# GaugeRev2.net
KiCad netlist of a schematic drawn in EAGLE
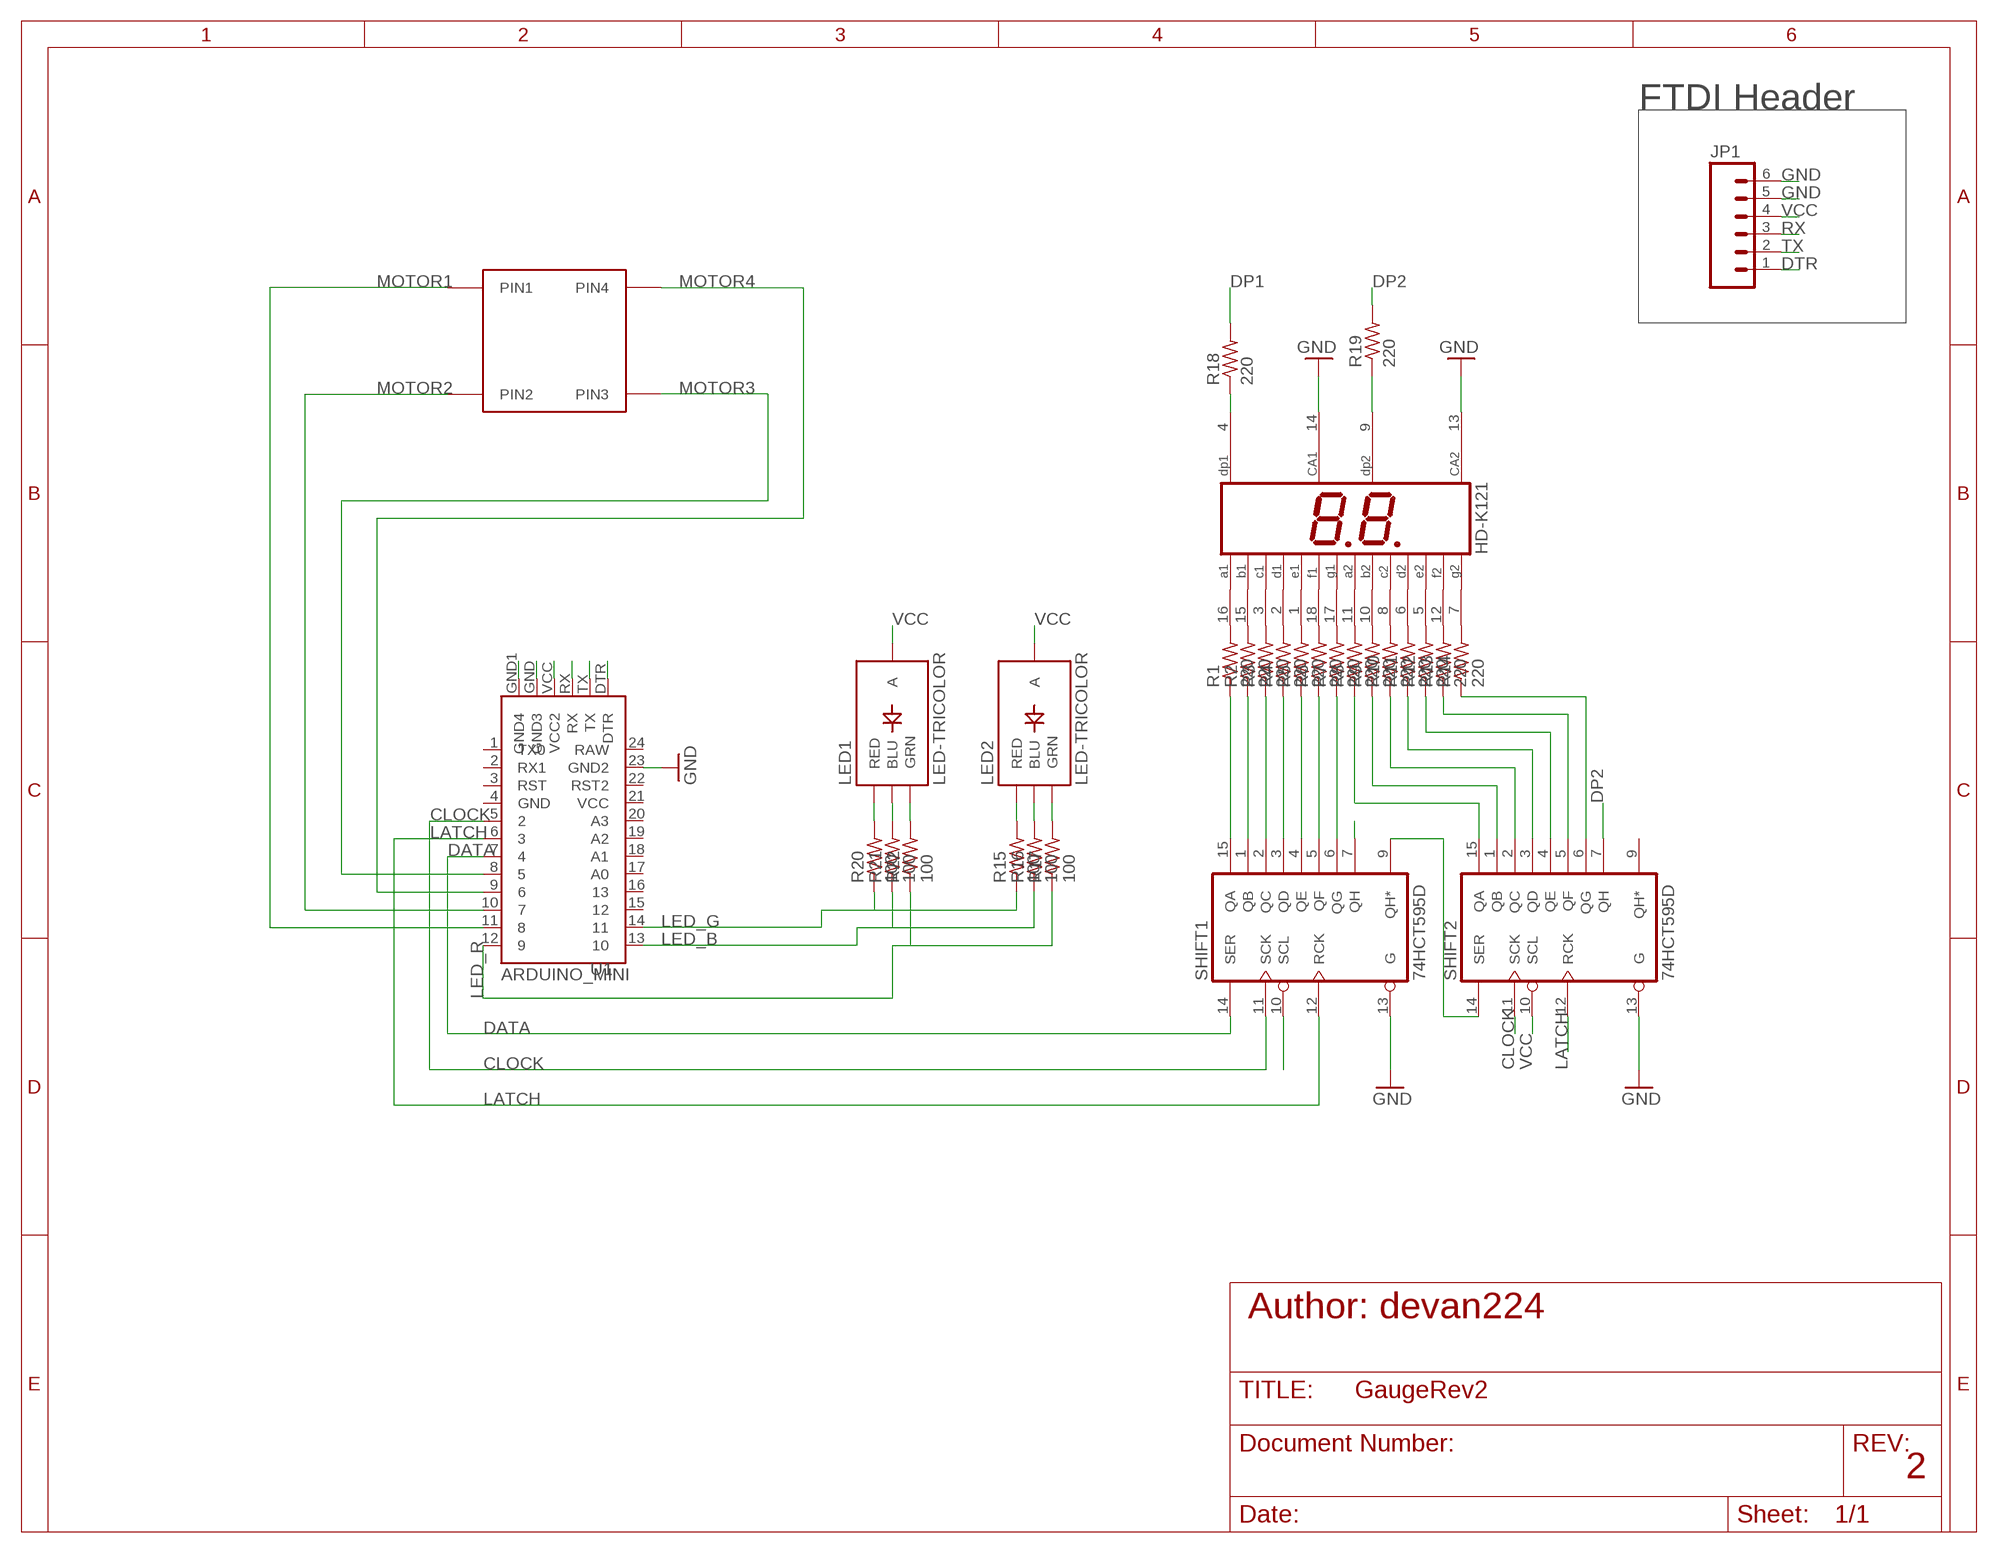
[diagram p0: schematic, sheet 1]

(export (version "E")
  (design (tool "Eeschema 10.0.6"))
  (components
    (comp (ref "DIS2")
      (value "HD-K121")
      (footprint "eagle-import:HDSP-R")
      (libsource (lib "eagle-import") (part "HD-K121"))
    )
    (comp (ref "JP1")
      (value "M06SIP")
      (footprint "eagle-import:1X06")
      (libsource (lib "eagle-import") (part "M06SIP"))
    )
    (comp (ref "LED1")
      (value "LED-TRICOLOR")
      (footprint "eagle-import:LED-TRICOLOR-SMD")
      (libsource (lib "eagle-import") (part "LED-TRICOLOR"))
    )
    (comp (ref "LED2")
      (value "LED-TRICOLOR")
      (footprint "eagle-import:LED-TRICOLOR-SMD")
      (libsource (lib "eagle-import") (part "LED-TRICOLOR"))
    )
    (comp (ref "R1")
      (value "220")
      (footprint "eagle-import:R1206")
      (libsource (lib "eagle-import") (part "R-US_R1206"))
    )
    (comp (ref "R2")
      (value "220")
      (footprint "eagle-import:R1206")
      (libsource (lib "eagle-import") (part "R-US_R1206"))
    )
    (comp (ref "R3")
      (value "220")
      (footprint "eagle-import:R1206")
      (libsource (lib "eagle-import") (part "R-US_R1206"))
    )
    (comp (ref "R4")
      (value "220")
      (footprint "eagle-import:R1206")
      (libsource (lib "eagle-import") (part "R-US_R1206"))
    )
    (comp (ref "R5")
      (value "220")
      (footprint "eagle-import:R1206")
      (libsource (lib "eagle-import") (part "R-US_R1206"))
    )
    (comp (ref "R6")
      (value "220")
      (footprint "eagle-import:R1206")
      (libsource (lib "eagle-import") (part "R-US_R1206"))
    )
    (comp (ref "R7")
      (value "220")
      (footprint "eagle-import:R1206")
      (libsource (lib "eagle-import") (part "R-US_R1206"))
    )
    (comp (ref "R8")
      (value "220")
      (footprint "eagle-import:R1206")
      (libsource (lib "eagle-import") (part "R-US_R1206"))
    )
    (comp (ref "R9")
      (value "220")
      (footprint "eagle-import:R1206")
      (libsource (lib "eagle-import") (part "R-US_R1206"))
    )
    (comp (ref "R10")
      (value "220")
      (footprint "eagle-import:R1206")
      (libsource (lib "eagle-import") (part "R-US_R1206"))
    )
    (comp (ref "R11")
      (value "220")
      (footprint "eagle-import:R1206")
      (libsource (lib "eagle-import") (part "R-US_R1206"))
    )
    (comp (ref "R12")
      (value "220")
      (footprint "eagle-import:R1206")
      (libsource (lib "eagle-import") (part "R-US_R1206"))
    )
    (comp (ref "R13")
      (value "220")
      (footprint "eagle-import:R1206")
      (libsource (lib "eagle-import") (part "R-US_R1206"))
    )
    (comp (ref "R14")
      (value "220")
      (footprint "eagle-import:R1206")
      (libsource (lib "eagle-import") (part "R-US_R1206"))
    )
    (comp (ref "R15")
      (value "100")
      (footprint "eagle-import:R1206")
      (libsource (lib "eagle-import") (part "R-US_R1206"))
    )
    (comp (ref "R16")
      (value "100")
      (footprint "eagle-import:R1206")
      (libsource (lib "eagle-import") (part "R-US_R1206"))
    )
    (comp (ref "R17")
      (value "100")
      (footprint "eagle-import:R1206")
      (libsource (lib "eagle-import") (part "R-US_R1206"))
    )
    (comp (ref "R18")
      (value "220")
      (footprint "eagle-import:R1206")
      (libsource (lib "eagle-import") (part "R-US_R1206"))
    )
    (comp (ref "R19")
      (value "220")
      (footprint "eagle-import:R1206")
      (libsource (lib "eagle-import") (part "R-US_R1206"))
    )
    (comp (ref "R20")
      (value "100")
      (footprint "eagle-import:R1206")
      (libsource (lib "eagle-import") (part "R-US_R1206"))
    )
    (comp (ref "R21")
      (value "100")
      (footprint "eagle-import:R1206")
      (libsource (lib "eagle-import") (part "R-US_R1206"))
    )
    (comp (ref "R22")
      (value "100")
      (footprint "eagle-import:R1206")
      (libsource (lib "eagle-import") (part "R-US_R1206"))
    )
    (comp (ref "SHIFT1")
      (value "74HCT595D")
      (footprint "eagle-import:SO16")
      (libsource (lib "eagle-import") (part "74595DHCT"))
    )
    (comp (ref "SHIFT2")
      (value "74HCT595D")
      (footprint "eagle-import:SO16")
      (libsource (lib "eagle-import") (part "74595DHCT"))
    )
    (comp (ref "U1")
      (value "ARDUINO_MINI")
      (footprint "eagle-import:ARDUINO_MINI")
      (libsource (lib "eagle-import") (part "ARDUINO_MINI"))
    )
    (comp (ref "U2")
      (value "VID29")
      (footprint "eagle-import:VID29")
      (libsource (lib "eagle-import") (part "VID29"))
    )
  )
  (nets
    (net (code "1") (name "/CLOCK") (class "Default")
      (node (ref "SHIFT1") (pin "11") (pinfunction "SCK_11") (pintype "input"))
      (node (ref "SHIFT2") (pin "11") (pinfunction "SCK_11") (pintype "input"))
      (node (ref "U1") (pin "5") (pinfunction "2_5") (pintype "bidirectional"))
    )
    (net (code "2") (name "/DATA") (class "Default")
      (node (ref "SHIFT1") (pin "14") (pinfunction "SER_14") (pintype "input"))
      (node (ref "U1") (pin "7") (pinfunction "4_7") (pintype "bidirectional"))
    )
    (net (code "3") (name "/DP1") (class "Default")
      (node (ref "R18") (pin "2") (pinfunction "2_2") (pintype "passive"))
      (node (ref "SHIFT1") (pin "7") (pinfunction "QH_7") (pintype "tri_state"))
    )
    (net (code "4") (name "/DP2") (class "Default")
      (node (ref "R19") (pin "2") (pinfunction "2_2") (pintype "passive"))
      (node (ref "SHIFT2") (pin "7") (pinfunction "QH_7") (pintype "tri_state"))
    )
    (net (code "5") (name "/DTR") (class "Default")
      (node (ref "JP1") (pin "1") (pinfunction "1_1") (pintype "passive"))
      (node (ref "U1") (pin "DTR") (pinfunction "DTR_DTR") (pintype "bidirectional"))
    )
    (net (code "6") (name "/LATCH") (class "Default")
      (node (ref "SHIFT1") (pin "12") (pinfunction "RCK_12") (pintype "input"))
      (node (ref "SHIFT2") (pin "12") (pinfunction "RCK_12") (pintype "input"))
      (node (ref "U1") (pin "6") (pinfunction "3_6") (pintype "bidirectional"))
    )
    (net (code "7") (name "/LED_B") (class "Default")
      (node (ref "R16") (pin "1") (pinfunction "1_1") (pintype "passive"))
      (node (ref "R21") (pin "1") (pinfunction "1_1") (pintype "passive"))
      (node (ref "U1") (pin "13") (pinfunction "10_13") (pintype "bidirectional"))
    )
    (net (code "8") (name "/LED_G") (class "Default")
      (node (ref "R15") (pin "1") (pinfunction "1_1") (pintype "passive"))
      (node (ref "R20") (pin "1") (pinfunction "1_1") (pintype "passive"))
      (node (ref "U1") (pin "14") (pinfunction "11_14") (pintype "bidirectional"))
    )
    (net (code "9") (name "/LED_R") (class "Default")
      (node (ref "R17") (pin "1") (pinfunction "1_1") (pintype "passive"))
      (node (ref "R22") (pin "1") (pinfunction "1_1") (pintype "passive"))
      (node (ref "U1") (pin "12") (pinfunction "9_12") (pintype "bidirectional"))
    )
    (net (code "10") (name "/MOTOR1") (class "Default")
      (node (ref "U1") (pin "11") (pinfunction "8_11") (pintype "bidirectional"))
      (node (ref "U2") (pin "PIN1") (pinfunction "PIN1_PIN1") (pintype "bidirectional"))
    )
    (net (code "11") (name "/MOTOR2") (class "Default")
      (node (ref "U1") (pin "10") (pinfunction "7_10") (pintype "bidirectional"))
      (node (ref "U2") (pin "PIN2") (pinfunction "PIN2_PIN2") (pintype "bidirectional"))
    )
    (net (code "12") (name "/MOTOR3") (class "Default")
      (node (ref "U1") (pin "8") (pinfunction "5_8") (pintype "bidirectional"))
      (node (ref "U2") (pin "PIN3") (pinfunction "PIN3_PIN3") (pintype "bidirectional"))
    )
    (net (code "13") (name "/MOTOR4") (class "Default")
      (node (ref "U1") (pin "9") (pinfunction "6_9") (pintype "bidirectional"))
      (node (ref "U2") (pin "PIN4") (pinfunction "PIN4_PIN4") (pintype "bidirectional"))
    )
    (net (code "14") (name "/RX") (class "Default")
      (node (ref "JP1") (pin "3") (pinfunction "3_3") (pintype "passive"))
      (node (ref "U1") (pin "RX") (pinfunction "RX_RX") (pintype "bidirectional"))
    )
    (net (code "15") (name "/TX") (class "Default")
      (node (ref "JP1") (pin "2") (pinfunction "2_2") (pintype "passive"))
      (node (ref "U1") (pin "TX") (pinfunction "TX_TX") (pintype "bidirectional"))
    )
    (net (code "16") (name "/VCC") (class "Default")
      (node (ref "JP1") (pin "4") (pinfunction "4_4") (pintype "passive"))
      (node (ref "LED1") (pin "A") (pinfunction "A_A") (pintype "bidirectional"))
      (node (ref "LED2") (pin "A") (pinfunction "A_A") (pintype "bidirectional"))
      (node (ref "SHIFT1") (pin "10") (pinfunction "SCL_10") (pintype "input"))
      (node (ref "SHIFT2") (pin "10") (pinfunction "SCL_10") (pintype "input"))
      (node (ref "U1") (pin "VCC") (pinfunction "VCC2_VCC") (pintype "bidirectional"))
    )
    (net (code "17") (name "GND") (class "Default")
      (node (ref "DIS2") (pin "13") (pinfunction "CA2_13") (pintype "passive"))
      (node (ref "DIS2") (pin "14") (pinfunction "CA1_14") (pintype "passive"))
      (node (ref "JP1") (pin "5") (pinfunction "5_5") (pintype "passive"))
      (node (ref "JP1") (pin "6") (pinfunction "6_6") (pintype "passive"))
      (node (ref "SHIFT1") (pin "13") (pinfunction "G_13") (pintype "input"))
      (node (ref "SHIFT2") (pin "13") (pinfunction "G_13") (pintype "input"))
      (node (ref "U1") (pin "23") (pinfunction "GND2_23") (pintype "bidirectional"))
      (node (ref "U1") (pin "GND") (pinfunction "GND3_GND") (pintype "bidirectional"))
      (node (ref "U1") (pin "GND1") (pinfunction "GND4_GND1") (pintype "bidirectional"))
    )
    (net (code "18") (name "Net-(DIS2-A1)") (class "Default")
      (node (ref "DIS2") (pin "16") (pinfunction "A1_16") (pintype "passive"))
      (node (ref "R1") (pin "2") (pinfunction "2_2") (pintype "passive"))
    )
    (net (code "19") (name "Net-(DIS2-A2)") (class "Default")
      (node (ref "DIS2") (pin "11") (pinfunction "A2_11") (pintype "passive"))
      (node (ref "R8") (pin "2") (pinfunction "2_2") (pintype "passive"))
    )
    (net (code "20") (name "Net-(DIS2-B1)") (class "Default")
      (node (ref "DIS2") (pin "15") (pinfunction "B1_15") (pintype "passive"))
      (node (ref "R2") (pin "2") (pinfunction "2_2") (pintype "passive"))
    )
    (net (code "21") (name "Net-(DIS2-B2)") (class "Default")
      (node (ref "DIS2") (pin "10") (pinfunction "B2_10") (pintype "passive"))
      (node (ref "R9") (pin "2") (pinfunction "2_2") (pintype "passive"))
    )
    (net (code "22") (name "Net-(DIS2-C1)") (class "Default")
      (node (ref "DIS2") (pin "3") (pinfunction "C1_3") (pintype "passive"))
      (node (ref "R3") (pin "2") (pinfunction "2_2") (pintype "passive"))
    )
    (net (code "23") (name "Net-(DIS2-C2)") (class "Default")
      (node (ref "DIS2") (pin "8") (pinfunction "C2_8") (pintype "passive"))
      (node (ref "R10") (pin "2") (pinfunction "2_2") (pintype "passive"))
    )
    (net (code "24") (name "Net-(DIS2-D1)") (class "Default")
      (node (ref "DIS2") (pin "2") (pinfunction "D1_2") (pintype "passive"))
      (node (ref "R4") (pin "2") (pinfunction "2_2") (pintype "passive"))
    )
    (net (code "25") (name "Net-(DIS2-D2)") (class "Default")
      (node (ref "DIS2") (pin "6") (pinfunction "D2_6") (pintype "passive"))
      (node (ref "R11") (pin "2") (pinfunction "2_2") (pintype "passive"))
    )
    (net (code "26") (name "Net-(DIS2-DP1)") (class "Default")
      (node (ref "DIS2") (pin "4") (pinfunction "DP1_4") (pintype "passive"))
      (node (ref "R18") (pin "1") (pinfunction "1_1") (pintype "passive"))
    )
    (net (code "27") (name "Net-(DIS2-DP2)") (class "Default")
      (node (ref "DIS2") (pin "9") (pinfunction "DP2_9") (pintype "passive"))
      (node (ref "R19") (pin "1") (pinfunction "1_1") (pintype "passive"))
    )
    (net (code "28") (name "Net-(DIS2-E1)") (class "Default")
      (node (ref "DIS2") (pin "1") (pinfunction "E1_1") (pintype "passive"))
      (node (ref "R5") (pin "2") (pinfunction "2_2") (pintype "passive"))
    )
    (net (code "29") (name "Net-(DIS2-E2)") (class "Default")
      (node (ref "DIS2") (pin "5") (pinfunction "E2_5") (pintype "passive"))
      (node (ref "R12") (pin "2") (pinfunction "2_2") (pintype "passive"))
    )
    (net (code "30") (name "Net-(DIS2-F1)") (class "Default")
      (node (ref "DIS2") (pin "18") (pinfunction "F1_18") (pintype "passive"))
      (node (ref "R6") (pin "2") (pinfunction "2_2") (pintype "passive"))
    )
    (net (code "31") (name "Net-(DIS2-F2)") (class "Default")
      (node (ref "DIS2") (pin "12") (pinfunction "F2_12") (pintype "passive"))
      (node (ref "R13") (pin "2") (pinfunction "2_2") (pintype "passive"))
    )
    (net (code "32") (name "Net-(DIS2-G1)") (class "Default")
      (node (ref "DIS2") (pin "17") (pinfunction "G1_17") (pintype "passive"))
      (node (ref "R7") (pin "2") (pinfunction "2_2") (pintype "passive"))
    )
    (net (code "33") (name "Net-(DIS2-G2)") (class "Default")
      (node (ref "DIS2") (pin "7") (pinfunction "G2_7") (pintype "passive"))
      (node (ref "R14") (pin "2") (pinfunction "2_2") (pintype "passive"))
    )
    (net (code "34") (name "Net-(LED1-BLU)") (class "Default")
      (node (ref "LED1") (pin "B") (pinfunction "BLU_B") (pintype "bidirectional"))
      (node (ref "R21") (pin "2") (pinfunction "2_2") (pintype "passive"))
    )
    (net (code "35") (name "Net-(LED1-GRN)") (class "Default")
      (node (ref "LED1") (pin "G") (pinfunction "GRN_G") (pintype "bidirectional"))
      (node (ref "R22") (pin "2") (pinfunction "2_2") (pintype "passive"))
    )
    (net (code "36") (name "Net-(LED1-RED)") (class "Default")
      (node (ref "LED1") (pin "R") (pinfunction "RED_R") (pintype "bidirectional"))
      (node (ref "R20") (pin "2") (pinfunction "2_2") (pintype "passive"))
    )
    (net (code "37") (name "Net-(LED2-BLU)") (class "Default")
      (node (ref "LED2") (pin "B") (pinfunction "BLU_B") (pintype "bidirectional"))
      (node (ref "R16") (pin "2") (pinfunction "2_2") (pintype "passive"))
    )
    (net (code "38") (name "Net-(LED2-GRN)") (class "Default")
      (node (ref "LED2") (pin "G") (pinfunction "GRN_G") (pintype "bidirectional"))
      (node (ref "R17") (pin "2") (pinfunction "2_2") (pintype "passive"))
    )
    (net (code "39") (name "Net-(LED2-RED)") (class "Default")
      (node (ref "LED2") (pin "R") (pinfunction "RED_R") (pintype "bidirectional"))
      (node (ref "R15") (pin "2") (pinfunction "2_2") (pintype "passive"))
    )
    (net (code "40") (name "Net-(SHIFT1A-QA)") (class "Default")
      (node (ref "R1") (pin "1") (pinfunction "1_1") (pintype "passive"))
      (node (ref "SHIFT1") (pin "15") (pinfunction "QA_15") (pintype "tri_state"))
    )
    (net (code "41") (name "Net-(SHIFT1A-QB)") (class "Default")
      (node (ref "R2") (pin "1") (pinfunction "1_1") (pintype "passive"))
      (node (ref "SHIFT1") (pin "1") (pinfunction "QB_1") (pintype "tri_state"))
    )
    (net (code "42") (name "Net-(SHIFT1A-QC)") (class "Default")
      (node (ref "R3") (pin "1") (pinfunction "1_1") (pintype "passive"))
      (node (ref "SHIFT1") (pin "2") (pinfunction "QC_2") (pintype "tri_state"))
    )
    (net (code "43") (name "Net-(SHIFT1A-QD)") (class "Default")
      (node (ref "R4") (pin "1") (pinfunction "1_1") (pintype "passive"))
      (node (ref "SHIFT1") (pin "3") (pinfunction "QD_3") (pintype "tri_state"))
    )
    (net (code "44") (name "Net-(SHIFT1A-QE)") (class "Default")
      (node (ref "R5") (pin "1") (pinfunction "1_1") (pintype "passive"))
      (node (ref "SHIFT1") (pin "4") (pinfunction "QE_4") (pintype "tri_state"))
    )
    (net (code "45") (name "Net-(SHIFT1A-QF)") (class "Default")
      (node (ref "R6") (pin "1") (pinfunction "1_1") (pintype "passive"))
      (node (ref "SHIFT1") (pin "5") (pinfunction "QF_5") (pintype "tri_state"))
    )
    (net (code "46") (name "Net-(SHIFT1A-QG)") (class "Default")
      (node (ref "R7") (pin "1") (pinfunction "1_1") (pintype "passive"))
      (node (ref "SHIFT1") (pin "6") (pinfunction "QG_6") (pintype "tri_state"))
    )
    (net (code "47") (name "Net-(SHIFT1A-QH*)") (class "Default")
      (node (ref "SHIFT1") (pin "9") (pinfunction "QH*_9") (pintype "tri_state"))
      (node (ref "SHIFT2") (pin "14") (pinfunction "SER_14") (pintype "input"))
    )
    (net (code "48") (name "Net-(SHIFT2A-QA)") (class "Default")
      (node (ref "R8") (pin "1") (pinfunction "1_1") (pintype "passive"))
      (node (ref "SHIFT2") (pin "15") (pinfunction "QA_15") (pintype "tri_state"))
    )
    (net (code "49") (name "Net-(SHIFT2A-QB)") (class "Default")
      (node (ref "R9") (pin "1") (pinfunction "1_1") (pintype "passive"))
      (node (ref "SHIFT2") (pin "1") (pinfunction "QB_1") (pintype "tri_state"))
    )
    (net (code "50") (name "Net-(SHIFT2A-QC)") (class "Default")
      (node (ref "R10") (pin "1") (pinfunction "1_1") (pintype "passive"))
      (node (ref "SHIFT2") (pin "2") (pinfunction "QC_2") (pintype "tri_state"))
    )
    (net (code "51") (name "Net-(SHIFT2A-QD)") (class "Default")
      (node (ref "R11") (pin "1") (pinfunction "1_1") (pintype "passive"))
      (node (ref "SHIFT2") (pin "3") (pinfunction "QD_3") (pintype "tri_state"))
    )
    (net (code "52") (name "Net-(SHIFT2A-QE)") (class "Default")
      (node (ref "R12") (pin "1") (pinfunction "1_1") (pintype "passive"))
      (node (ref "SHIFT2") (pin "4") (pinfunction "QE_4") (pintype "tri_state"))
    )
    (net (code "53") (name "Net-(SHIFT2A-QF)") (class "Default")
      (node (ref "R13") (pin "1") (pinfunction "1_1") (pintype "passive"))
      (node (ref "SHIFT2") (pin "5") (pinfunction "QF_5") (pintype "tri_state"))
    )
    (net (code "54") (name "Net-(SHIFT2A-QG)") (class "Default")
      (node (ref "R14") (pin "1") (pinfunction "1_1") (pintype "passive"))
      (node (ref "SHIFT2") (pin "6") (pinfunction "QG_6") (pintype "tri_state"))
    )
    (net (code "55") (name "unconnected-(SHIFT2A-QH*-Pad9)") (class "Default")
      (node (ref "SHIFT2") (pin "9") (pinfunction "QH*_9") (pintype "tri_state"))
    )
    (net (code "56") (name "unconnected-(U1-12-Pad15)") (class "Default")
      (node (ref "U1") (pin "15") (pinfunction "12_15") (pintype "bidirectional"))
    )
    (net (code "57") (name "unconnected-(U1-13-Pad16)") (class "Default")
      (node (ref "U1") (pin "16") (pinfunction "13_16") (pintype "bidirectional"))
    )
    (net (code "58") (name "unconnected-(U1-A0-Pad17)") (class "Default")
      (node (ref "U1") (pin "17") (pinfunction "A0_17") (pintype "bidirectional"))
    )
    (net (code "59") (name "unconnected-(U1-A1-Pad18)") (class "Default")
      (node (ref "U1") (pin "18") (pinfunction "A1_18") (pintype "bidirectional"))
    )
    (net (code "60") (name "unconnected-(U1-A2-Pad19)") (class "Default")
      (node (ref "U1") (pin "19") (pinfunction "A2_19") (pintype "bidirectional"))
    )
    (net (code "61") (name "unconnected-(U1-A3-Pad20)") (class "Default")
      (node (ref "U1") (pin "20") (pinfunction "A3_20") (pintype "bidirectional"))
    )
    (net (code "62") (name "unconnected-(U1-GND-Pad4)") (class "Default")
      (node (ref "U1") (pin "4") (pinfunction "GND_4") (pintype "bidirectional"))
    )
    (net (code "63") (name "unconnected-(U1-RAW-Pad24)") (class "Default")
      (node (ref "U1") (pin "24") (pinfunction "RAW_24") (pintype "bidirectional"))
    )
    (net (code "64") (name "unconnected-(U1-RST-Pad3)") (class "Default")
      (node (ref "U1") (pin "3") (pinfunction "RST_3") (pintype "bidirectional"))
    )
    (net (code "65") (name "unconnected-(U1-RST2-Pad22)") (class "Default")
      (node (ref "U1") (pin "22") (pinfunction "RST2_22") (pintype "bidirectional"))
    )
    (net (code "66") (name "unconnected-(U1-RX1-Pad2)") (class "Default")
      (node (ref "U1") (pin "2") (pinfunction "RX1_2") (pintype "bidirectional"))
    )
    (net (code "67") (name "unconnected-(U1-TX0-Pad1)") (class "Default")
      (node (ref "U1") (pin "1") (pinfunction "TX0_1") (pintype "bidirectional"))
    )
    (net (code "68") (name "unconnected-(U1-VCC-Pad21)") (class "Default")
      (node (ref "U1") (pin "21") (pinfunction "VCC_21") (pintype "bidirectional"))
    )
  )
)
